# LC_LPF6.net
KiCad netlist of a schematic drawn in Altium Designer
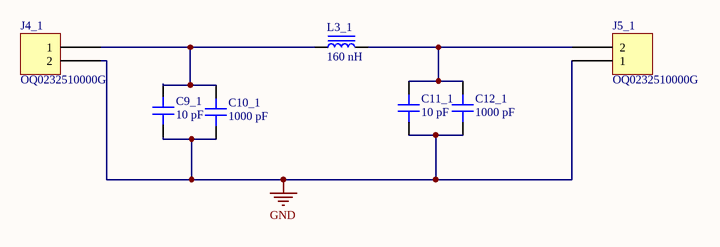
[diagram p0: LC_LPF6.SchDoc]

(export (version "E")
  (design (tool "Eeschema 10.0.6"))
  (components
    (comp (ref "C9_1")
      (value "10 pF")
      (footprint "CAP 0603_1608")
      (description "CAP CER 10PF 100V C0G/NPO 0603")
      (fields (field (name "PART NUMBER") "AC0603JRNPO0BN100") (field (name "MANUFACTURER") "Yageo"))
      (libsource (lib "Celestial Altium Library - altium_library") (part "Capacitor"))
    )
    (comp (ref "C10_1")
      (value "1000 pF")
      (footprint "CAP 0603_1608")
      (description "CAP CER 1000PF 100V X7R 0603")
      (fields
        (field (name "PART NUMBER") "GCD188R72A102KA01D")
        (field (name "MANUFACTURER") "Murata Electronics")
      )
      (libsource (lib "Celestial Altium Library - altium_library") (part "Capacitor"))
    )
    (comp (ref "C11_1")
      (value "10 pF")
      (footprint "CAP 0603_1608")
      (description "CAP CER 10PF 100V C0G/NPO 0603")
      (fields (field (name "PART NUMBER") "AC0603JRNPO0BN100") (field (name "MANUFACTURER") "Yageo"))
      (libsource (lib "Celestial Altium Library - altium_library") (part "Capacitor"))
    )
    (comp (ref "C12_1")
      (value "1000 pF")
      (footprint "CAP 0603_1608")
      (description "CAP CER 1000PF 100V X7R 0603")
      (fields
        (field (name "PART NUMBER") "GCD188R72A102KA01D")
        (field (name "MANUFACTURER") "Murata Electronics")
      )
      (libsource (lib "Celestial Altium Library - altium_library") (part "Capacitor"))
    )
    (comp (ref "J4_1")
      (value "OQ0232510000G")
      (footprint "FCI 06-381-2PIN")
      (description "TERM BLOCK HDR 2POS 90DEG 3.81MM")
      (fields (field (name "MANUFACTURER") "Amphenol Anytek"))
      (libsource (lib "") (part "2 Pin_1"))
    )
    (comp (ref "J5_1")
      (value "OQ0232510000G")
      (footprint "FCI 06-381-2PIN")
      (description "TERM BLOCK HDR 2POS 90DEG 3.81MM")
      (fields (field (name "MANUFACTURER") "Amphenol Anytek"))
      (libsource (lib "Celestial Altium Library - altium_library") (part "2 Pin"))
    )
    (comp (ref "L3_1")
      (value "160 nH")
      (footprint "IND 0402_1005 RF WW")
      (description "FIXED IND 160NH 480MA 330MOHM SM")
      (fields
        (field (name "PART NUMBER") "LQW15CNR16J00D")
        (field (name "MANUFACTURER") "Murata Electronics")
      )
      (libsource (lib "Celestial Altium Library - altium_library") (part "Inductor"))
    )
  )
  (nets
    (net (code "1") (name "GND") (class "Default")
      (node (ref "C10_1") (pin "2") (pinfunction "2_2") (pintype "passive"))
      (node (ref "C11_1") (pin "1") (pinfunction "1_1") (pintype "passive"))
      (node (ref "C12_1") (pin "2") (pinfunction "2_2") (pintype "passive"))
      (node (ref "C9_1") (pin "1") (pinfunction "1_1") (pintype "passive"))
      (node (ref "J4_1") (pin "2") (pinfunction "2_2") (pintype "passive"))
      (node (ref "J5_1") (pin "1") (pinfunction "1_1") (pintype "passive"))
    )
    (net (code "2") (name "Net-(C10_1-Pad1)") (class "Default")
      (node (ref "C10_1") (pin "1") (pinfunction "1_1") (pintype "passive"))
      (node (ref "C9_1") (pin "2") (pinfunction "2_2") (pintype "passive"))
      (node (ref "J4_1") (pin "1") (pinfunction "1_1") (pintype "passive"))
      (node (ref "L3_1") (pin "1") (pinfunction "1_1") (pintype "passive"))
    )
    (net (code "3") (name "Net-(C11_1-Pad2)") (class "Default")
      (node (ref "C11_1") (pin "2") (pinfunction "2_2") (pintype "passive"))
      (node (ref "C12_1") (pin "1") (pinfunction "1_1") (pintype "passive"))
      (node (ref "J5_1") (pin "2") (pinfunction "2_2") (pintype "passive"))
      (node (ref "L3_1") (pin "2") (pinfunction "2_2") (pintype "passive"))
    )
  )
)
